# WaterTemp.net
KiCad netlist of a schematic drawn in EAGLE
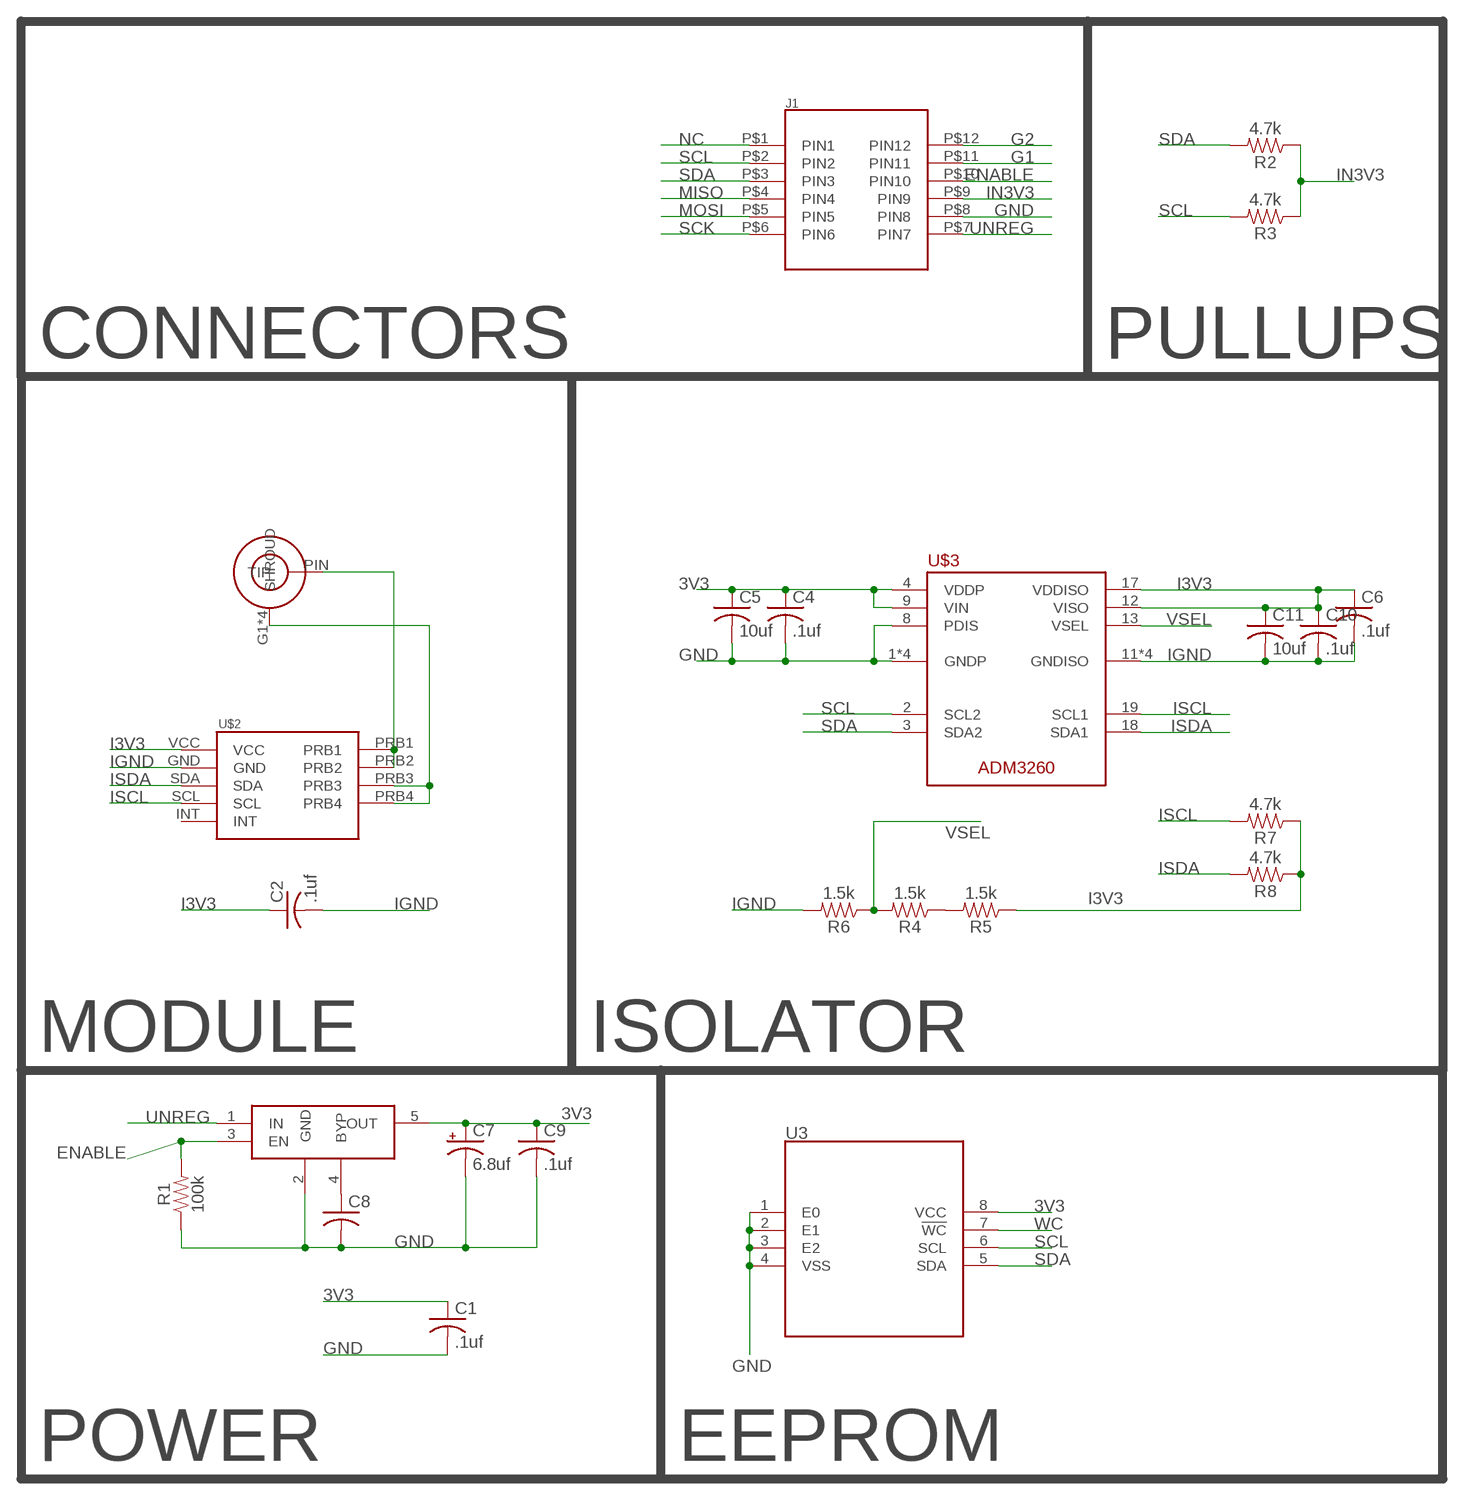
[diagram p0: schematic, sheet 1]

(export (version "E")
  (design (tool "Eeschema 10.0.6"))
  (components
    (comp (ref "C1")
      (value ".1uf")
      (footprint "eagle-import:C0603K")
      (libsource (lib "eagle-import") (part "C-USC0603K"))
    )
    (comp (ref "C2")
      (value ".1uf")
      (footprint "eagle-import:C0603K")
      (libsource (lib "eagle-import") (part "C-USC0603K"))
    )
    (comp (ref "C4")
      (value ".1uf")
      (footprint "eagle-import:C0603K")
      (libsource (lib "eagle-import") (part "C-USC0603K"))
    )
    (comp (ref "C5")
      (value "10uf")
      (footprint "eagle-import:C0603K")
      (libsource (lib "eagle-import") (part "C-USC0603K"))
    )
    (comp (ref "C6")
      (value ".1uf")
      (footprint "eagle-import:C0603K")
      (libsource (lib "eagle-import") (part "C-USC0603K"))
    )
    (comp (ref "C7")
      (value "6.8uf")
      (footprint "eagle-import:A_3216-18R")
      (libsource (lib "eagle-import") (part "CPOL-USA/3216-18R"))
    )
    (comp (ref "C8")
      (value "C-USC0603K")
      (footprint "eagle-import:C0603K")
      (libsource (lib "eagle-import") (part "C-USC0603K"))
    )
    (comp (ref "C9")
      (value ".1uf")
      (footprint "eagle-import:C0603K")
      (libsource (lib "eagle-import") (part "C-USC0603K"))
    )
    (comp (ref "C10")
      (value ".1uf")
      (footprint "eagle-import:C0603K")
      (libsource (lib "eagle-import") (part "C-USC0603K"))
    )
    (comp (ref "C11")
      (value "10uf")
      (footprint "eagle-import:C0603K")
      (libsource (lib "eagle-import") (part "C-USC0603K"))
    )
    (comp (ref "J1")
      (value "2X6-HEADERS")
      (footprint "eagle-import:M20-7810645")
      (libsource (lib "eagle-import") (part "2X6-HEADERS"))
    )
    (comp (ref "R1")
      (value "100k")
      (footprint "eagle-import:0603")
      (libsource (lib "eagle-import") (part "100KOHM-0603-1/10W-1%"))
    )
    (comp (ref "R2")
      (value "4.7k")
      (footprint "eagle-import:0603")
      (libsource (lib "eagle-import") (part "100KOHM-0603-1/10W-1%"))
    )
    (comp (ref "R3")
      (value "4.7k")
      (footprint "eagle-import:0603")
      (libsource (lib "eagle-import") (part "100KOHM-0603-1/10W-1%"))
    )
    (comp (ref "R4")
      (value "1.5k")
      (footprint "eagle-import:0603")
      (libsource (lib "eagle-import") (part "100KOHM-0603-1/10W-1%"))
    )
    (comp (ref "R5")
      (value "1.5k")
      (footprint "eagle-import:0603")
      (libsource (lib "eagle-import") (part "100KOHM-0603-1/10W-1%"))
    )
    (comp (ref "R6")
      (value "1.5k")
      (footprint "eagle-import:0603")
      (libsource (lib "eagle-import") (part "100KOHM-0603-1/10W-1%"))
    )
    (comp (ref "R7")
      (value "4.7k")
      (footprint "eagle-import:0603")
      (libsource (lib "eagle-import") (part "100KOHM-0603-1/10W-1%"))
    )
    (comp (ref "R8")
      (value "4.7k")
      (footprint "eagle-import:0603")
      (libsource (lib "eagle-import") (part "100KOHM-0603-1/10W-1%"))
    )
    (comp (ref "U$1")
      (value "5-1814832-1")
      (footprint "eagle-import:5-1814832-1")
      (libsource (lib "eagle-import") (part "5-1814832-1"))
    )
    (comp (ref "U$2")
      (value "ATLAS12P")
      (footprint "eagle-import:ATLAS-12P")
      (libsource (lib "eagle-import") (part "ATLAS12P"))
    )
    (comp (ref "U$3")
      (value "ADM3260")
      (footprint "eagle-import:SOP65P780X200-20")
      (libsource (lib "eagle-import") (part "ADM3260"))
    )
    (comp (ref "U$4")
      (value "MIC5219-3.3YM5-TR")
      (footprint "eagle-import:SOT95P280X145-5")
      (libsource (lib "eagle-import") (part "MIC5219-3.3YM5-TR"))
    )
    (comp (ref "U3")
      (value "M24C02-WMN6TP")
      (footprint "eagle-import:SOIC127P600X175-8")
      (libsource (lib "eagle-import") (part "M24C02-WMN6TP"))
    )
  )
  (nets
    (net (code "1") (name "/3V3") (class "Default")
      (node (ref "C1") (pin "1") (pinfunction "1_1") (pintype "passive"))
      (node (ref "C4") (pin "1") (pinfunction "1_1") (pintype "passive"))
      (node (ref "C5") (pin "1") (pinfunction "1_1") (pintype "passive"))
      (node (ref "C7") (pin "+") (pinfunction "+_+") (pintype "passive"))
      (node (ref "C9") (pin "1") (pinfunction "1_1") (pintype "passive"))
      (node (ref "U$3") (pin "4") (pinfunction "VDDP_4") (pintype "bidirectional"))
      (node (ref "U$3") (pin "9") (pinfunction "VIN_9") (pintype "bidirectional"))
      (node (ref "U$4") (pin "5") (pinfunction "OUT_5") (pintype "bidirectional"))
      (node (ref "U3") (pin "8") (pinfunction "VCC_8") (pintype "bidirectional"))
    )
    (net (code "2") (name "/ENABLE") (class "Default")
      (node (ref "J1") (pin "P$10") (pinfunction "PIN10_P$10") (pintype "bidirectional"))
      (node (ref "R1") (pin "2") (pinfunction "2_2") (pintype "passive"))
      (node (ref "U$4") (pin "3") (pinfunction "EN_3") (pintype "bidirectional"))
    )
    (net (code "3") (name "/G1") (class "Default")
      (node (ref "J1") (pin "P$11") (pinfunction "PIN11_P$11") (pintype "bidirectional"))
    )
    (net (code "4") (name "/G2") (class "Default")
      (node (ref "J1") (pin "P$12") (pinfunction "PIN12_P$12") (pintype "bidirectional"))
    )
    (net (code "5") (name "/GND") (class "Default")
      (node (ref "C1") (pin "2") (pinfunction "2_2") (pintype "passive"))
      (node (ref "C4") (pin "2") (pinfunction "2_2") (pintype "passive"))
      (node (ref "C5") (pin "2") (pinfunction "2_2") (pintype "passive"))
      (node (ref "C7") (pin "-") (pinfunction "-_-") (pintype "passive"))
      (node (ref "C8") (pin "2") (pinfunction "2_2") (pintype "passive"))
      (node (ref "C9") (pin "2") (pinfunction "2_2") (pintype "passive"))
      (node (ref "J1") (pin "P$8") (pinfunction "PIN8_P$8") (pintype "bidirectional"))
      (node (ref "R1") (pin "1") (pinfunction "1_1") (pintype "passive"))
      (node (ref "U$3") (pin "1") (pinfunction "GNDP_1") (pintype "bidirectional"))
      (node (ref "U$3") (pin "10") (pinfunction "GNDP_10") (pintype "bidirectional"))
      (node (ref "U$3") (pin "5") (pinfunction "GNDP_5") (pintype "bidirectional"))
      (node (ref "U$3") (pin "7") (pinfunction "GNDP_7") (pintype "bidirectional"))
      (node (ref "U$3") (pin "8") (pinfunction "PDIS_8") (pintype "bidirectional"))
      (node (ref "U$4") (pin "2") (pinfunction "GND_2") (pintype "bidirectional"))
      (node (ref "U3") (pin "1") (pinfunction "E0_1") (pintype "bidirectional"))
      (node (ref "U3") (pin "2") (pinfunction "E1_2") (pintype "bidirectional"))
      (node (ref "U3") (pin "3") (pinfunction "E2_3") (pintype "bidirectional"))
      (node (ref "U3") (pin "4") (pinfunction "VSS_4") (pintype "bidirectional"))
    )
    (net (code "6") (name "/I3V3") (class "Default")
      (node (ref "C10") (pin "1") (pinfunction "1_1") (pintype "passive"))
      (node (ref "C11") (pin "1") (pinfunction "1_1") (pintype "passive"))
      (node (ref "C2") (pin "1") (pinfunction "1_1") (pintype "passive"))
      (node (ref "C6") (pin "1") (pinfunction "1_1") (pintype "passive"))
      (node (ref "R5") (pin "1") (pinfunction "1_1") (pintype "passive"))
      (node (ref "R7") (pin "1") (pinfunction "1_1") (pintype "passive"))
      (node (ref "R8") (pin "1") (pinfunction "1_1") (pintype "passive"))
      (node (ref "U$2") (pin "VCC") (pinfunction "VCC_VCC") (pintype "bidirectional"))
      (node (ref "U$3") (pin "12") (pinfunction "VISO_12") (pintype "bidirectional"))
      (node (ref "U$3") (pin "17") (pinfunction "VDDISO_17") (pintype "bidirectional"))
    )
    (net (code "7") (name "/IGND") (class "Default")
      (node (ref "C10") (pin "2") (pinfunction "2_2") (pintype "passive"))
      (node (ref "C11") (pin "2") (pinfunction "2_2") (pintype "passive"))
      (node (ref "C2") (pin "2") (pinfunction "2_2") (pintype "passive"))
      (node (ref "C6") (pin "2") (pinfunction "2_2") (pintype "passive"))
      (node (ref "R6") (pin "2") (pinfunction "2_2") (pintype "passive"))
      (node (ref "U$2") (pin "GND") (pinfunction "GND_GND") (pintype "bidirectional"))
      (node (ref "U$3") (pin "11") (pinfunction "GNDISO_11") (pintype "bidirectional"))
      (node (ref "U$3") (pin "14") (pinfunction "GNDISO_14") (pintype "bidirectional"))
      (node (ref "U$3") (pin "16") (pinfunction "GNDISO_16") (pintype "bidirectional"))
      (node (ref "U$3") (pin "20") (pinfunction "GNDISO_20") (pintype "bidirectional"))
    )
    (net (code "8") (name "/IN3V3") (class "Default")
      (node (ref "J1") (pin "P$9") (pinfunction "PIN9_P$9") (pintype "bidirectional"))
      (node (ref "R2") (pin "1") (pinfunction "1_1") (pintype "passive"))
      (node (ref "R3") (pin "1") (pinfunction "1_1") (pintype "passive"))
    )
    (net (code "9") (name "/ISCL") (class "Default")
      (node (ref "R7") (pin "2") (pinfunction "2_2") (pintype "passive"))
      (node (ref "U$2") (pin "SCL") (pinfunction "SCL_SCL") (pintype "bidirectional"))
      (node (ref "U$3") (pin "19") (pinfunction "SCL1_19") (pintype "bidirectional"))
    )
    (net (code "10") (name "/ISDA") (class "Default")
      (node (ref "R8") (pin "2") (pinfunction "2_2") (pintype "passive"))
      (node (ref "U$2") (pin "SDA") (pinfunction "SDA_SDA") (pintype "bidirectional"))
      (node (ref "U$3") (pin "18") (pinfunction "SDA1_18") (pintype "bidirectional"))
    )
    (net (code "11") (name "/MISO") (class "Default")
      (node (ref "J1") (pin "P$4") (pinfunction "PIN4_P$4") (pintype "bidirectional"))
    )
    (net (code "12") (name "/MOSI") (class "Default")
      (node (ref "J1") (pin "P$5") (pinfunction "PIN5_P$5") (pintype "bidirectional"))
    )
    (net (code "13") (name "/NC") (class "Default")
      (node (ref "J1") (pin "P$1") (pinfunction "PIN1_P$1") (pintype "bidirectional"))
    )
    (net (code "14") (name "/SCK") (class "Default")
      (node (ref "J1") (pin "P$6") (pinfunction "PIN6_P$6") (pintype "bidirectional"))
    )
    (net (code "15") (name "/SCL") (class "Default")
      (node (ref "J1") (pin "P$2") (pinfunction "PIN2_P$2") (pintype "bidirectional"))
      (node (ref "R3") (pin "2") (pinfunction "2_2") (pintype "passive"))
      (node (ref "U$3") (pin "2") (pinfunction "SCL2_2") (pintype "bidirectional"))
      (node (ref "U3") (pin "6") (pinfunction "SCL_6") (pintype "bidirectional"))
    )
    (net (code "16") (name "/SDA") (class "Default")
      (node (ref "J1") (pin "P$3") (pinfunction "PIN3_P$3") (pintype "bidirectional"))
      (node (ref "R2") (pin "2") (pinfunction "2_2") (pintype "passive"))
      (node (ref "U$3") (pin "3") (pinfunction "SDA2_3") (pintype "bidirectional"))
      (node (ref "U3") (pin "5") (pinfunction "SDA_5") (pintype "bidirectional"))
    )
    (net (code "17") (name "/UNREG") (class "Default")
      (node (ref "J1") (pin "P$7") (pinfunction "PIN7_P$7") (pintype "bidirectional"))
      (node (ref "U$4") (pin "1") (pinfunction "IN_1") (pintype "bidirectional"))
    )
    (net (code "18") (name "/VSEL") (class "Default")
      (node (ref "R4") (pin "2") (pinfunction "2_2") (pintype "passive"))
      (node (ref "R6") (pin "1") (pinfunction "1_1") (pintype "passive"))
      (node (ref "U$3") (pin "13") (pinfunction "VSEL_13") (pintype "bidirectional"))
    )
    (net (code "19") (name "/WC") (class "Default")
      (node (ref "U3") (pin "7") (pinfunction "~{WC}_7") (pintype "bidirectional"))
    )
    (net (code "20") (name "Net-(R4-Pad1)") (class "Default")
      (node (ref "R4") (pin "1") (pinfunction "1_1") (pintype "passive"))
      (node (ref "R5") (pin "2") (pinfunction "2_2") (pintype "passive"))
    )
    (net (code "21") (name "Net-(U$1-SHROUD-PadG1)") (class "Default")
      (node (ref "U$1") (pin "G1") (pinfunction "SHROUD_G1") (pintype "bidirectional"))
      (node (ref "U$1") (pin "G2") (pinfunction "SHROUD_G2") (pintype "bidirectional"))
      (node (ref "U$1") (pin "G3") (pinfunction "SHROUD_G3") (pintype "bidirectional"))
      (node (ref "U$1") (pin "G4") (pinfunction "SHROUD_G4") (pintype "bidirectional"))
      (node (ref "U$2") (pin "PRB3") (pinfunction "PRB3_PRB3") (pintype "bidirectional"))
      (node (ref "U$2") (pin "PRB4") (pinfunction "PRB4_PRB4") (pintype "bidirectional"))
    )
    (net (code "22") (name "Net-(U$1-TIP)") (class "Default")
      (node (ref "U$1") (pin "PIN") (pinfunction "TIP_PIN") (pintype "bidirectional"))
      (node (ref "U$2") (pin "PRB1") (pinfunction "PRB1_PRB1") (pintype "bidirectional"))
      (node (ref "U$2") (pin "PRB2") (pinfunction "PRB2_PRB2") (pintype "bidirectional"))
    )
    (net (code "23") (name "Net-(U$4-BYP)") (class "Default")
      (node (ref "C8") (pin "1") (pinfunction "1_1") (pintype "passive"))
      (node (ref "U$4") (pin "4") (pinfunction "BYP_4") (pintype "bidirectional"))
    )
    (net (code "24") (name "unconnected-(U$2-PadINT)") (class "Default")
      (node (ref "U$2") (pin "INT") (pinfunction "INT_INT") (pintype "bidirectional"))
    )
  )
)
